# KNoT-Gateway_Starter_Board.net
KiCad netlist of a schematic drawn in Altium Designer
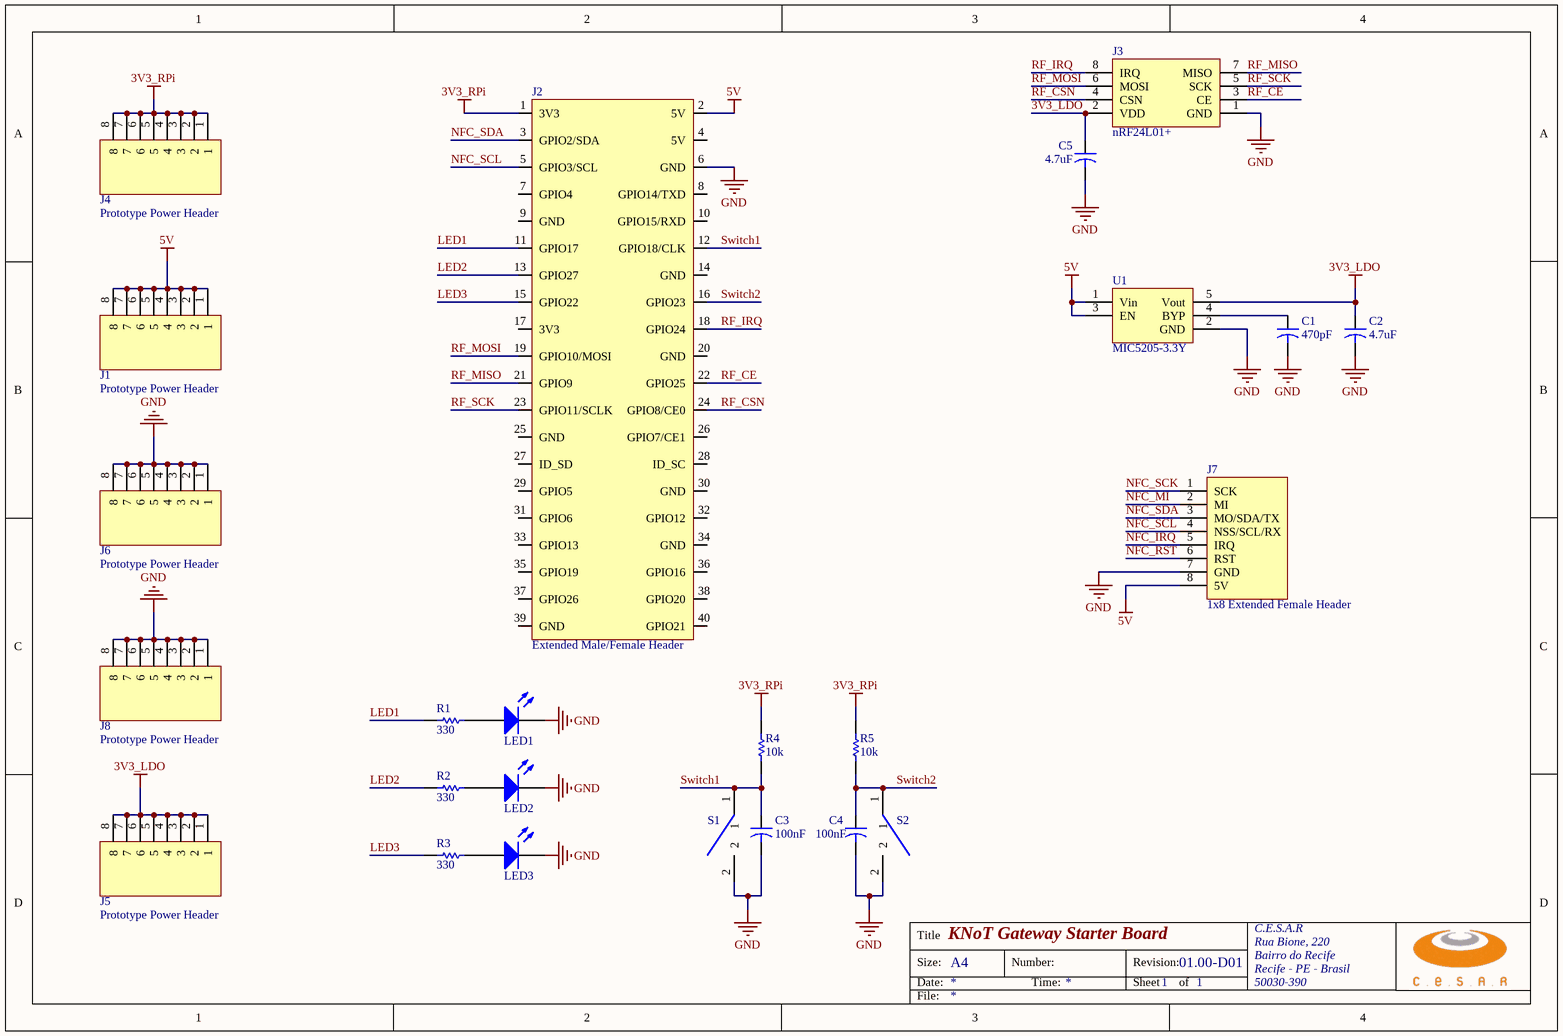
[diagram p0: KNoT-Gateway Starter Board.SchDoc]

(export (version "E")
  (design (tool "Eeschema 10.0.6"))
  (components
    (comp (ref "C1")
      (value "470pF")
      (footprint "CAPC1608L")
      (description "4.7µF 10V Ceramic Capacitor X5R 0603")
      (fields (field (name "Comment") "Cap0603") (field (name "PUBLISHER") "Altium Limited"))
      (libsource (lib "KNoT-Gateway Library") (part "Cap0603"))
    )
    (comp (ref "C2")
      (value "4.7uF")
      (footprint "CAPC1608L")
      (description "4.7µF 10V Ceramic Capacitor X5R 0603")
      (fields (field (name "Comment") "Cap0603") (field (name "PUBLISHER") "Altium Limited"))
      (libsource (lib "KNoT-Gateway Library") (part "Cap0603"))
    )
    (comp (ref "C3")
      (value "100nF")
      (footprint "CAPC1608L")
      (description "4.7µF 10V Ceramic Capacitor X5R 0603")
      (fields (field (name "Comment") "Cap0603") (field (name "PUBLISHER") "Altium Limited"))
      (libsource (lib "KNoT-Gateway Library") (part "Cap0603"))
    )
    (comp (ref "C4")
      (value "100nF")
      (footprint "CAPC1608L")
      (description "4.7µF 10V Ceramic Capacitor X5R 0603")
      (fields (field (name "Comment") "Cap0603") (field (name "PUBLISHER") "Altium Limited"))
      (libsource (lib "KNoT-Gateway Library") (part "Cap0603"))
    )
    (comp (ref "C5")
      (value "4.7uF")
      (footprint "CAPC1608L")
      (description "4.7µF 10V Ceramic Capacitor X5R 0603")
      (fields (field (name "Comment") "Cap0603") (field (name "PUBLISHER") "Altium Limited"))
      (libsource (lib "KNoT-Gateway Library") (part "Cap0603"))
    )
    (comp (ref "J1")
      (value "Prototype Power Header")
      (footprint "Prototype Holes 1X8")
      (libsource (lib "KNoT-Gateway Library") (part "Prototype Power Header"))
    )
    (comp (ref "J2")
      (value "Extended Male/Female Header")
      (footprint "FEMALE HEADER 2X20")
      (description "RPi GPIO HEADER 2X20")
      (libsource (lib "KNoT-Gateway Library") (part "RPI2_GPIO"))
    )
    (comp (ref "J3")
      (value "nRF24L01+")
      (footprint "nRF24L01+PA+LNA")
      (description "nRF24L01 2x4 HEADER")
      (libsource (lib "KNoT-Gateway Library") (part "nRF24L01+"))
    )
    (comp (ref "J4")
      (value "Prototype Power Header")
      (footprint "Prototype Holes 1X8")
      (libsource (lib "KNoT-Gateway Library") (part "Prototype Power Header"))
    )
    (comp (ref "J5")
      (value "Prototype Power Header")
      (footprint "Prototype Holes 1X8")
      (libsource (lib "KNoT-Gateway Library") (part "Prototype Power Header"))
    )
    (comp (ref "J6")
      (value "Prototype Power Header")
      (footprint "Prototype Holes 1X8")
      (libsource (lib "KNoT-Gateway Library") (part "Prototype Power Header"))
    )
    (comp (ref "J7")
      (value "1x8 Extended Female Header")
      (footprint "NFC_ITEAD_PN532")
      (description "PN532_NFC")
      (libsource (lib "KNoT-Gateway Library") (part "PN532_NFC"))
    )
    (comp (ref "J8")
      (value "Prototype Power Header")
      (footprint "Prototype Holes 1X8")
      (libsource (lib "KNoT-Gateway Library") (part "Prototype Power Header"))
    )
    (comp (ref "LED1")
      (value "LED PTH")
      (footprint "LED PTH")
      (libsource (lib "KNoT-Gateway Library") (part "LED 0603"))
    )
    (comp (ref "LED2")
      (value "LED PTH")
      (footprint "LED PTH")
      (libsource (lib "KNoT-Gateway Library") (part "LED 0603"))
    )
    (comp (ref "LED3")
      (value "LED PTH")
      (footprint "LED PTH")
      (libsource (lib "KNoT-Gateway Library") (part "LED 0603"))
    )
    (comp (ref "R1")
      (value "330")
      (footprint "CAPC1608L")
      (fields (field (name "Comment") "RES_0402"))
      (libsource (lib "KNoT-Gateway Library") (part "RES_0402"))
    )
    (comp (ref "R2")
      (value "330")
      (footprint "CAPC1608L")
      (fields (field (name "Comment") "RES_0402"))
      (libsource (lib "KNoT-Gateway Library") (part "RES_0402"))
    )
    (comp (ref "R3")
      (value "330")
      (footprint "CAPC1608L")
      (fields (field (name "Comment") "RES_0402"))
      (libsource (lib "KNoT-Gateway Library") (part "RES_0402"))
    )
    (comp (ref "R4")
      (value "10k")
      (footprint "CAPC1608L")
      (fields (field (name "Comment") "RES_0402"))
      (libsource (lib "KNoT-Gateway Library") (part "RES_0402"))
    )
    (comp (ref "R5")
      (value "10k")
      (footprint "CAPC1608L")
      (fields (field (name "Comment") "RES_0402"))
      (libsource (lib "KNoT-Gateway Library") (part "RES_0402"))
    )
    (comp (ref "S1")
      (value "200mils Push Button PTH")
      (footprint "Push-Button PTH")
      (description "Push Button")
      (libsource (lib "KNoT-Gateway Library") (part "Push-Button PTH"))
    )
    (comp (ref "S2")
      (value "200mils Push Button PTH")
      (footprint "Push-Button PTH")
      (description "Push Button")
      (libsource (lib "KNoT-Gateway Library") (part "Push-Button PTH"))
    )
    (comp (ref "U1")
      (value "MIC5205-3.3Y")
      (footprint "SOT23-5")
      (description "MIC5205-3.3Y LDO")
      (libsource (lib "KNoT-Gateway Library") (part "MIC5205-3V3"))
    )
  )
  (nets
    (net (code "1") (name "/LED1") (class "Default")
      (node (ref "J2") (pin "11") (pinfunction "GPIO17_11") (pintype "passive"))
      (node (ref "R1") (pin "2") (pinfunction "2_2") (pintype "passive"))
    )
    (net (code "2") (name "/LED2") (class "Default")
      (node (ref "J2") (pin "13") (pinfunction "GPIO27_13") (pintype "passive"))
      (node (ref "R2") (pin "2") (pinfunction "2_2") (pintype "passive"))
    )
    (net (code "3") (name "/LED3") (class "Default")
      (node (ref "J2") (pin "15") (pinfunction "GPIO22_15") (pintype "passive"))
      (node (ref "R3") (pin "2") (pinfunction "2_2") (pintype "passive"))
    )
    (net (code "4") (name "/NFC_IRQ") (class "Default")
      (node (ref "J7") (pin "5") (pinfunction "IRQ_5") (pintype "passive"))
    )
    (net (code "5") (name "/NFC_MI") (class "Default")
      (node (ref "J7") (pin "2") (pinfunction "MI_2") (pintype "passive"))
    )
    (net (code "6") (name "/NFC_RST") (class "Default")
      (node (ref "J7") (pin "6") (pinfunction "RST_6") (pintype "passive"))
    )
    (net (code "7") (name "/NFC_SCK") (class "Default")
      (node (ref "J7") (pin "1") (pinfunction "SCK_1") (pintype "passive"))
    )
    (net (code "8") (name "/NFC_SCL") (class "Default")
      (node (ref "J2") (pin "5") (pinfunction "GPIO3/SCL_5") (pintype "passive"))
      (node (ref "J7") (pin "4") (pinfunction "NSS/SCL/RX_4") (pintype "passive"))
    )
    (net (code "9") (name "/NFC_SDA") (class "Default")
      (node (ref "J2") (pin "3") (pinfunction "GPIO2/SDA_3") (pintype "passive"))
      (node (ref "J7") (pin "3") (pinfunction "MO/SDA/TX_3") (pintype "passive"))
    )
    (net (code "10") (name "/RF_CE") (class "Default")
      (node (ref "J2") (pin "22") (pinfunction "GPIO25_22") (pintype "passive"))
      (node (ref "J3") (pin "3") (pinfunction "CE_3") (pintype "passive"))
    )
    (net (code "11") (name "/RF_CSN") (class "Default")
      (node (ref "J2") (pin "24") (pinfunction "GPIO8/CE0_24") (pintype "passive"))
      (node (ref "J3") (pin "4") (pinfunction "CSN_4") (pintype "passive"))
    )
    (net (code "12") (name "/RF_IRQ") (class "Default")
      (node (ref "J2") (pin "18") (pinfunction "GPIO24_18") (pintype "passive"))
      (node (ref "J3") (pin "8") (pinfunction "IRQ_8") (pintype "passive"))
    )
    (net (code "13") (name "/RF_MISO") (class "Default")
      (node (ref "J2") (pin "21") (pinfunction "GPIO9_21") (pintype "passive"))
      (node (ref "J3") (pin "7") (pinfunction "MISO_7") (pintype "passive"))
    )
    (net (code "14") (name "/RF_MOSI") (class "Default")
      (node (ref "J2") (pin "19") (pinfunction "GPIO10/MOSI_19") (pintype "passive"))
      (node (ref "J3") (pin "6") (pinfunction "MOSI_6") (pintype "passive"))
    )
    (net (code "15") (name "/RF_SCK") (class "Default")
      (node (ref "J2") (pin "23") (pinfunction "GPIO11/SCLK_23") (pintype "passive"))
      (node (ref "J3") (pin "5") (pinfunction "SCK_5") (pintype "passive"))
    )
    (net (code "16") (name "/Switch1") (class "Default")
      (node (ref "C3") (pin "1") (pinfunction "1_1") (pintype "passive"))
      (node (ref "J2") (pin "12") (pinfunction "GPIO18/CLK_12") (pintype "passive"))
      (node (ref "R4") (pin "2") (pinfunction "2_2") (pintype "passive"))
      (node (ref "S1") (pin "1") (pinfunction "1_1") (pintype "passive"))
    )
    (net (code "17") (name "/Switch2") (class "Default")
      (node (ref "C4") (pin "1") (pinfunction "1_1") (pintype "passive"))
      (node (ref "J2") (pin "16") (pinfunction "GPIO23_16") (pintype "passive"))
      (node (ref "R5") (pin "2") (pinfunction "2_2") (pintype "passive"))
      (node (ref "S2") (pin "1") (pinfunction "1_1") (pintype "passive"))
    )
    (net (code "18") (name "3V3_LDO") (class "Default")
      (node (ref "C2") (pin "1") (pinfunction "1_1") (pintype "passive"))
      (node (ref "C5") (pin "1") (pinfunction "1_1") (pintype "passive"))
      (node (ref "J3") (pin "2") (pinfunction "VDD_2") (pintype "passive"))
      (node (ref "J5") (pin "1") (pinfunction "1_1") (pintype "passive"))
      (node (ref "J5") (pin "2") (pinfunction "2_2") (pintype "passive"))
      (node (ref "J5") (pin "3") (pinfunction "3_3") (pintype "passive"))
      (node (ref "J5") (pin "4") (pinfunction "4_4") (pintype "passive"))
      (node (ref "J5") (pin "5") (pinfunction "5_5") (pintype "passive"))
      (node (ref "J5") (pin "6") (pinfunction "6_6") (pintype "passive"))
      (node (ref "J5") (pin "7") (pinfunction "7_7") (pintype "passive"))
      (node (ref "J5") (pin "8") (pinfunction "8_8") (pintype "passive"))
      (node (ref "U1") (pin "5") (pinfunction "Vout_5") (pintype "passive"))
    )
    (net (code "19") (name "3V3_RPi") (class "Default")
      (node (ref "J2") (pin "1") (pinfunction "3V3_1") (pintype "passive"))
      (node (ref "J4") (pin "1") (pinfunction "1_1") (pintype "passive"))
      (node (ref "J4") (pin "2") (pinfunction "2_2") (pintype "passive"))
      (node (ref "J4") (pin "3") (pinfunction "3_3") (pintype "passive"))
      (node (ref "J4") (pin "4") (pinfunction "4_4") (pintype "passive"))
      (node (ref "J4") (pin "5") (pinfunction "5_5") (pintype "passive"))
      (node (ref "J4") (pin "6") (pinfunction "6_6") (pintype "passive"))
      (node (ref "J4") (pin "7") (pinfunction "7_7") (pintype "passive"))
      (node (ref "J4") (pin "8") (pinfunction "8_8") (pintype "passive"))
      (node (ref "R4") (pin "1") (pinfunction "1_1") (pintype "passive"))
      (node (ref "R5") (pin "1") (pinfunction "1_1") (pintype "passive"))
    )
    (net (code "20") (name "5V") (class "Default")
      (node (ref "J1") (pin "1") (pinfunction "1_1") (pintype "passive"))
      (node (ref "J1") (pin "2") (pinfunction "2_2") (pintype "passive"))
      (node (ref "J1") (pin "3") (pinfunction "3_3") (pintype "passive"))
      (node (ref "J1") (pin "4") (pinfunction "4_4") (pintype "passive"))
      (node (ref "J1") (pin "5") (pinfunction "5_5") (pintype "passive"))
      (node (ref "J1") (pin "6") (pinfunction "6_6") (pintype "passive"))
      (node (ref "J1") (pin "7") (pinfunction "7_7") (pintype "passive"))
      (node (ref "J1") (pin "8") (pinfunction "8_8") (pintype "passive"))
      (node (ref "J2") (pin "2") (pinfunction "5V_2") (pintype "passive"))
      (node (ref "J7") (pin "8") (pinfunction "5V_8") (pintype "passive"))
      (node (ref "U1") (pin "1") (pinfunction "Vin_1") (pintype "passive"))
      (node (ref "U1") (pin "3") (pinfunction "EN_3") (pintype "passive"))
    )
    (net (code "21") (name "GND") (class "Default")
      (node (ref "C1") (pin "2") (pinfunction "2_2") (pintype "passive"))
      (node (ref "C2") (pin "2") (pinfunction "2_2") (pintype "passive"))
      (node (ref "C3") (pin "2") (pinfunction "2_2") (pintype "passive"))
      (node (ref "C4") (pin "2") (pinfunction "2_2") (pintype "passive"))
      (node (ref "C5") (pin "2") (pinfunction "2_2") (pintype "passive"))
      (node (ref "J2") (pin "6") (pinfunction "GND_6") (pintype "passive"))
      (node (ref "J3") (pin "1") (pinfunction "GND_1") (pintype "passive"))
      (node (ref "J6") (pin "1") (pinfunction "1_1") (pintype "passive"))
      (node (ref "J6") (pin "2") (pinfunction "2_2") (pintype "passive"))
      (node (ref "J6") (pin "3") (pinfunction "3_3") (pintype "passive"))
      (node (ref "J6") (pin "4") (pinfunction "4_4") (pintype "passive"))
      (node (ref "J6") (pin "5") (pinfunction "5_5") (pintype "passive"))
      (node (ref "J6") (pin "6") (pinfunction "6_6") (pintype "passive"))
      (node (ref "J6") (pin "7") (pinfunction "7_7") (pintype "passive"))
      (node (ref "J6") (pin "8") (pinfunction "8_8") (pintype "passive"))
      (node (ref "J7") (pin "7") (pinfunction "GND_7") (pintype "passive"))
      (node (ref "J8") (pin "1") (pinfunction "1_1") (pintype "passive"))
      (node (ref "J8") (pin "2") (pinfunction "2_2") (pintype "passive"))
      (node (ref "J8") (pin "3") (pinfunction "3_3") (pintype "passive"))
      (node (ref "J8") (pin "4") (pinfunction "4_4") (pintype "passive"))
      (node (ref "J8") (pin "5") (pinfunction "5_5") (pintype "passive"))
      (node (ref "J8") (pin "6") (pinfunction "6_6") (pintype "passive"))
      (node (ref "J8") (pin "7") (pinfunction "7_7") (pintype "passive"))
      (node (ref "J8") (pin "8") (pinfunction "8_8") (pintype "passive"))
      (node (ref "LED1") (pin "2") (pinfunction "K_2") (pintype "passive"))
      (node (ref "LED2") (pin "2") (pinfunction "K_2") (pintype "passive"))
      (node (ref "LED3") (pin "2") (pinfunction "K_2") (pintype "passive"))
      (node (ref "S1") (pin "2") (pinfunction "2_2") (pintype "passive"))
      (node (ref "S2") (pin "2") (pinfunction "2_2") (pintype "passive"))
      (node (ref "U1") (pin "2") (pinfunction "GND_2") (pintype "passive"))
    )
    (net (code "22") (name "Net-(LED1-A)") (class "Default")
      (node (ref "LED1") (pin "1") (pinfunction "A_1") (pintype "passive"))
      (node (ref "R1") (pin "1") (pinfunction "1_1") (pintype "passive"))
    )
    (net (code "23") (name "Net-(LED2-A)") (class "Default")
      (node (ref "LED2") (pin "1") (pinfunction "A_1") (pintype "passive"))
      (node (ref "R2") (pin "1") (pinfunction "1_1") (pintype "passive"))
    )
    (net (code "24") (name "Net-(LED3-A)") (class "Default")
      (node (ref "LED3") (pin "1") (pinfunction "A_1") (pintype "passive"))
      (node (ref "R3") (pin "1") (pinfunction "1_1") (pintype "passive"))
    )
    (net (code "25") (name "Net-(U1-BYP)") (class "Default")
      (node (ref "C1") (pin "1") (pinfunction "1_1") (pintype "passive"))
      (node (ref "U1") (pin "4") (pinfunction "BYP_4") (pintype "passive"))
    )
    (net (code "26") (name "unconnected-(J2-3V3-Pad17)") (class "Default")
      (node (ref "J2") (pin "17") (pinfunction "3V3_17") (pintype "passive"))
    )
    (net (code "27") (name "unconnected-(J2-5V-Pad4)") (class "Default")
      (node (ref "J2") (pin "4") (pinfunction "5V_4") (pintype "passive"))
    )
    (net (code "28") (name "unconnected-(J2-GND-Pad9)") (class "Default")
      (node (ref "J2") (pin "9") (pinfunction "GND_9") (pintype "passive"))
    )
    (net (code "29") (name "unconnected-(J2-GND-Pad14)") (class "Default")
      (node (ref "J2") (pin "14") (pinfunction "GND_14") (pintype "passive"))
    )
    (net (code "30") (name "unconnected-(J2-GND-Pad20)") (class "Default")
      (node (ref "J2") (pin "20") (pinfunction "GND_20") (pintype "passive"))
    )
    (net (code "31") (name "unconnected-(J2-GND-Pad25)") (class "Default")
      (node (ref "J2") (pin "25") (pinfunction "GND_25") (pintype "passive"))
    )
    (net (code "32") (name "unconnected-(J2-GND-Pad30)") (class "Default")
      (node (ref "J2") (pin "30") (pinfunction "GND_30") (pintype "passive"))
    )
    (net (code "33") (name "unconnected-(J2-GND-Pad34)") (class "Default")
      (node (ref "J2") (pin "34") (pinfunction "GND_34") (pintype "passive"))
    )
    (net (code "34") (name "unconnected-(J2-GND-Pad39)") (class "Default")
      (node (ref "J2") (pin "39") (pinfunction "GND_39") (pintype "passive"))
    )
    (net (code "35") (name "unconnected-(J2-GPIO4-Pad7)") (class "Default")
      (node (ref "J2") (pin "7") (pinfunction "GPIO4_7") (pintype "passive"))
    )
    (net (code "36") (name "unconnected-(J2-GPIO5-Pad29)") (class "Default")
      (node (ref "J2") (pin "29") (pinfunction "GPIO5_29") (pintype "passive"))
    )
    (net (code "37") (name "unconnected-(J2-GPIO6-Pad31)") (class "Default")
      (node (ref "J2") (pin "31") (pinfunction "GPIO6_31") (pintype "passive"))
    )
    (net (code "38") (name "unconnected-(J2-GPIO7{slash}CE1-Pad26)") (class "Default")
      (node (ref "J2") (pin "26") (pinfunction "GPIO7/CE1_26") (pintype "passive"))
    )
    (net (code "39") (name "unconnected-(J2-GPIO12-Pad32)") (class "Default")
      (node (ref "J2") (pin "32") (pinfunction "GPIO12_32") (pintype "passive"))
    )
    (net (code "40") (name "unconnected-(J2-GPIO13-Pad33)") (class "Default")
      (node (ref "J2") (pin "33") (pinfunction "GPIO13_33") (pintype "passive"))
    )
    (net (code "41") (name "unconnected-(J2-GPIO14{slash}TXD-Pad8)") (class "Default")
      (node (ref "J2") (pin "8") (pinfunction "GPIO14/TXD_8") (pintype "passive"))
    )
    (net (code "42") (name "unconnected-(J2-GPIO15{slash}RXD-Pad10)") (class "Default")
      (node (ref "J2") (pin "10") (pinfunction "GPIO15/RXD_10") (pintype "passive"))
    )
    (net (code "43") (name "unconnected-(J2-GPIO16-Pad36)") (class "Default")
      (node (ref "J2") (pin "36") (pinfunction "GPIO16_36") (pintype "passive"))
    )
    (net (code "44") (name "unconnected-(J2-GPIO19-Pad35)") (class "Default")
      (node (ref "J2") (pin "35") (pinfunction "GPIO19_35") (pintype "passive"))
    )
    (net (code "45") (name "unconnected-(J2-GPIO20-Pad38)") (class "Default")
      (node (ref "J2") (pin "38") (pinfunction "GPIO20_38") (pintype "passive"))
    )
    (net (code "46") (name "unconnected-(J2-GPIO21-Pad40)") (class "Default")
      (node (ref "J2") (pin "40") (pinfunction "GPIO21_40") (pintype "passive"))
    )
    (net (code "47") (name "unconnected-(J2-GPIO26-Pad37)") (class "Default")
      (node (ref "J2") (pin "37") (pinfunction "GPIO26_37") (pintype "passive"))
    )
    (net (code "48") (name "unconnected-(J2-ID_SC-Pad28)") (class "Default")
      (node (ref "J2") (pin "28") (pinfunction "ID_SC_28") (pintype "passive"))
    )
    (net (code "49") (name "unconnected-(J2-ID_SD-Pad27)") (class "Default")
      (node (ref "J2") (pin "27") (pinfunction "ID_SD_27") (pintype "passive"))
    )
  )
)
